# mixer-MAC-24.net
KiCad netlist of a schematic drawn in EAGLE
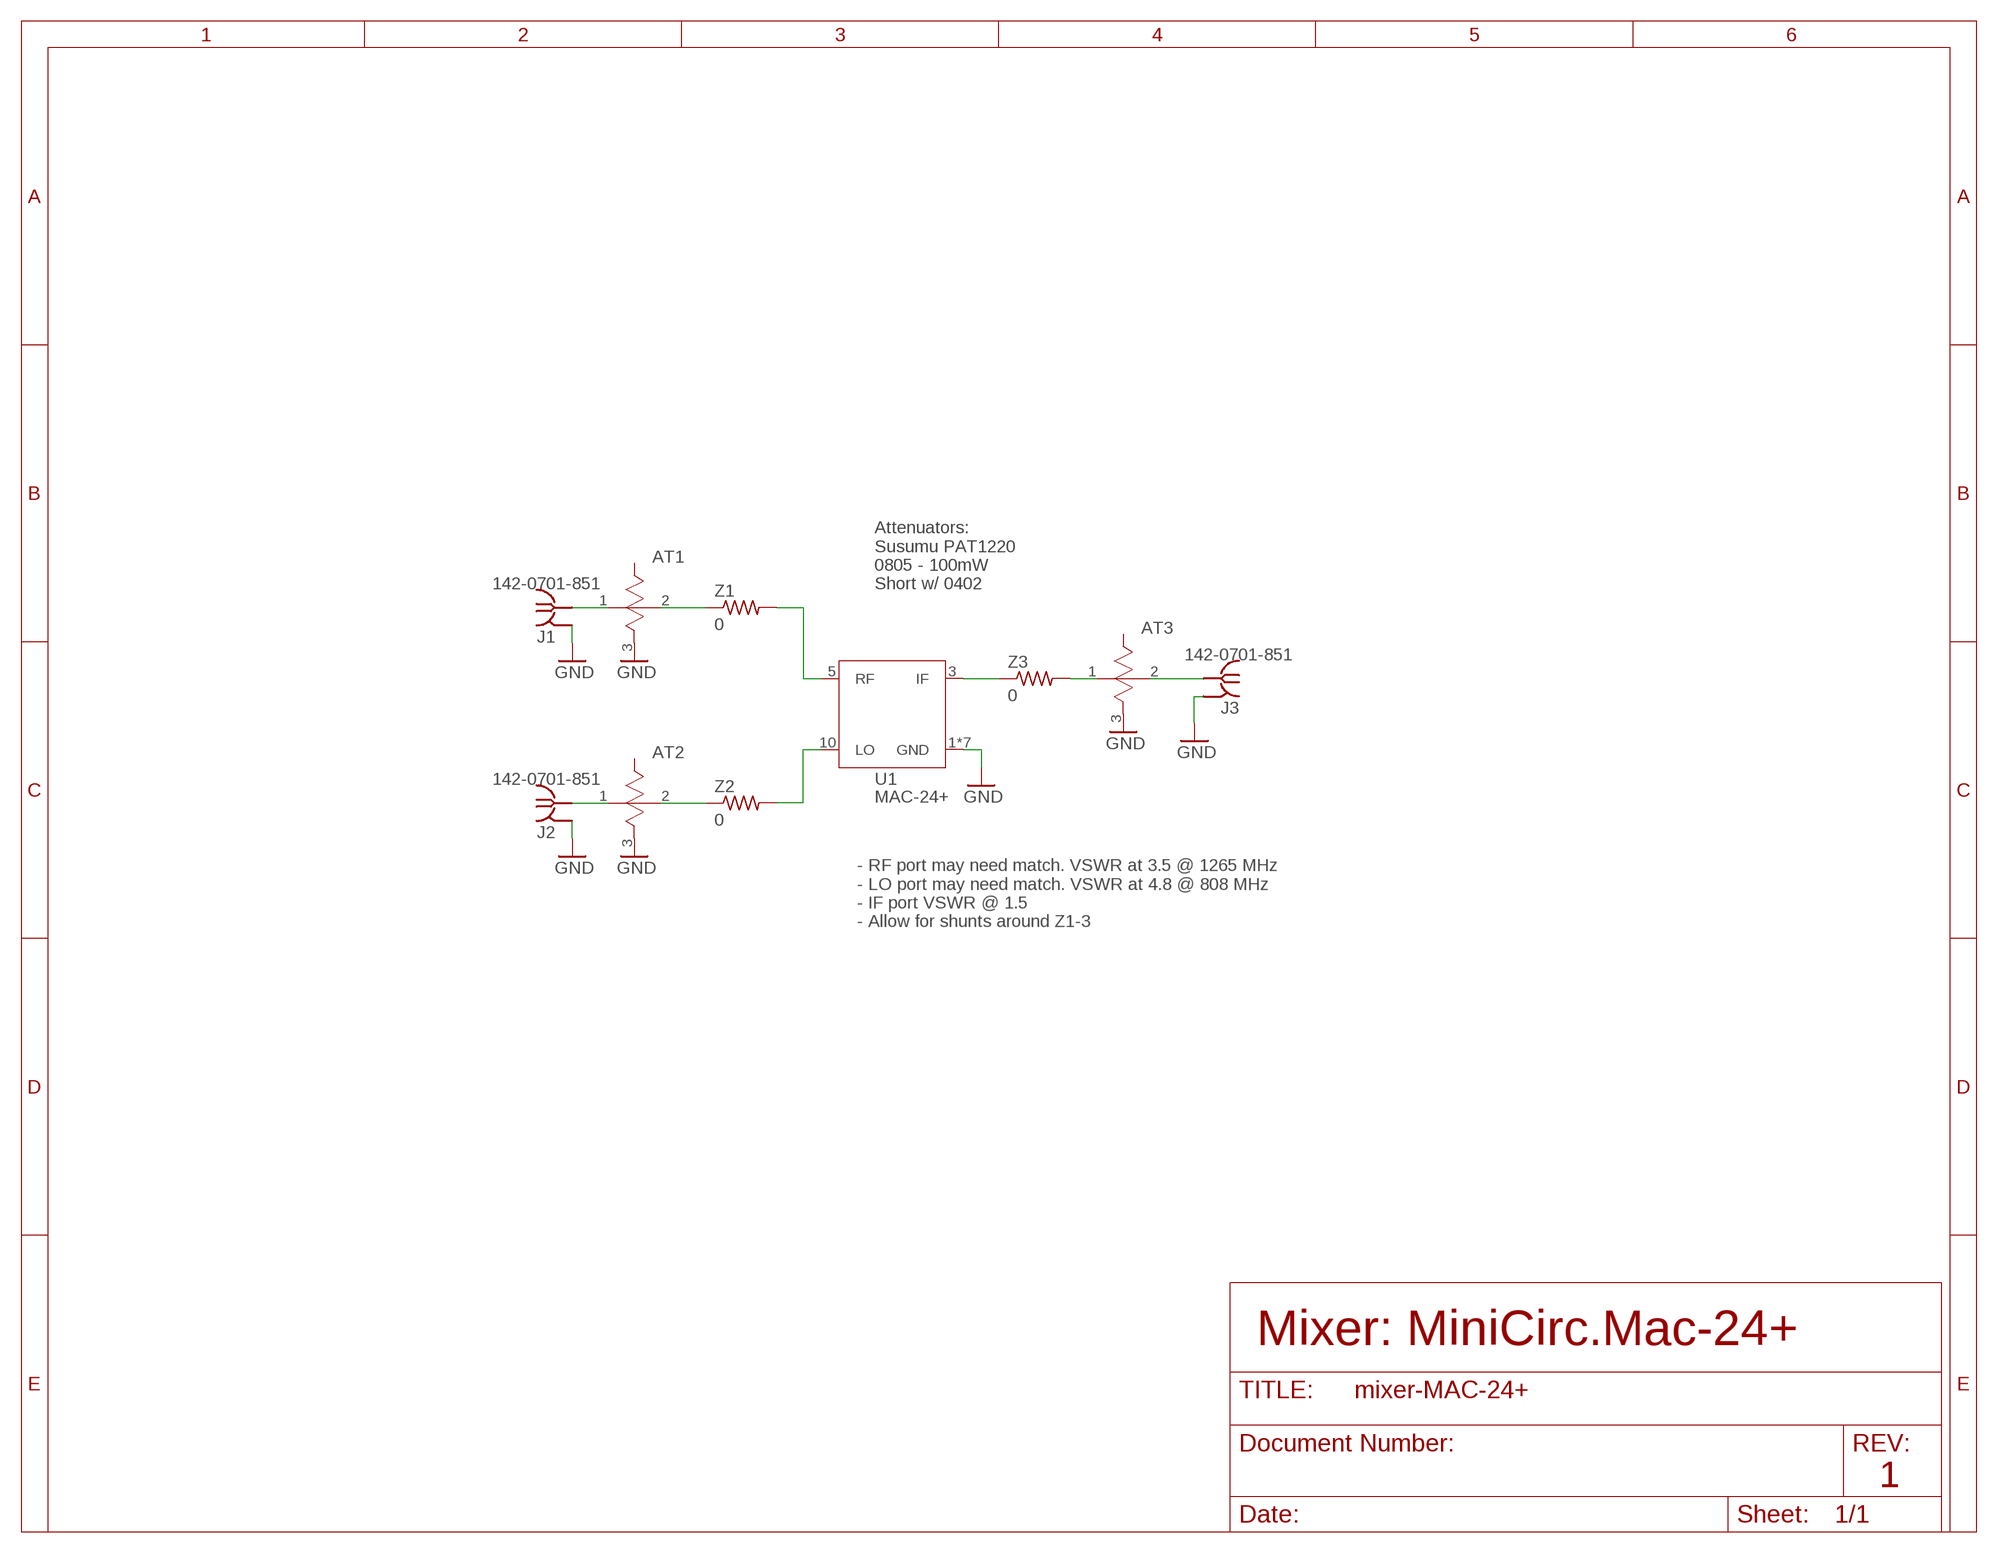
[diagram p0: schematic, sheet 1]

(export (version "E")
  (design (tool "Eeschema 10.0.6"))
  (components
    (comp (ref "AT1")
      (value "PAT1220")
      (footprint "eagle-import:0805")
      (libsource (lib "eagle-import") (part "PAT1220"))
    )
    (comp (ref "AT2")
      (value "PAT1220")
      (footprint "eagle-import:0805")
      (libsource (lib "eagle-import") (part "PAT1220"))
    )
    (comp (ref "AT3")
      (value "PAT1220")
      (footprint "eagle-import:0805")
      (libsource (lib "eagle-import") (part "PAT1220"))
    )
    (comp (ref "J1")
      (value "142-0701-851")
      (footprint "eagle-import:142-0701-851")
      (libsource (lib "eagle-import") (part "142-0701-851"))
    )
    (comp (ref "J2")
      (value "142-0701-851")
      (footprint "eagle-import:142-0701-851")
      (libsource (lib "eagle-import") (part "142-0701-851"))
    )
    (comp (ref "J3")
      (value "142-0701-851")
      (footprint "eagle-import:142-0701-851")
      (libsource (lib "eagle-import") (part "142-0701-851"))
    )
    (comp (ref "U1")
      (value "MAC-24+")
      (footprint "eagle-import:MAC-24+")
      (libsource (lib "eagle-import") (part "MAC-24+"))
    )
    (comp (ref "Z1")
      (value "0")
      (footprint "eagle-import:.0402-C-NOSILK")
      (libsource (lib "eagle-import") (part "R-US_0402-C-NOSILK"))
    )
    (comp (ref "Z2")
      (value "0")
      (footprint "eagle-import:.0402-C-NOSILK")
      (libsource (lib "eagle-import") (part "R-US_0402-C-NOSILK"))
    )
    (comp (ref "Z3")
      (value "0")
      (footprint "eagle-import:.0402-C-NOSILK")
      (libsource (lib "eagle-import") (part "R-US_0402-C-NOSILK"))
    )
  )
  (nets
    (net (code "1") (name "GND") (class "Default")
      (node (ref "AT1") (pin "3") (pinfunction "GND_3") (pintype "power_in"))
      (node (ref "AT2") (pin "3") (pinfunction "GND_3") (pintype "power_in"))
      (node (ref "AT3") (pin "3") (pinfunction "GND_3") (pintype "power_in"))
      (node (ref "J1") (pin "GND1") (pinfunction "GND_GND1") (pintype "bidirectional"))
      (node (ref "J1") (pin "GND2") (pinfunction "GND_GND2") (pintype "bidirectional"))
      (node (ref "J1") (pin "GND3") (pinfunction "GND_GND3") (pintype "bidirectional"))
      (node (ref "J1") (pin "GND4") (pinfunction "GND_GND4") (pintype "bidirectional"))
      (node (ref "J2") (pin "GND1") (pinfunction "GND_GND1") (pintype "bidirectional"))
      (node (ref "J2") (pin "GND2") (pinfunction "GND_GND2") (pintype "bidirectional"))
      (node (ref "J2") (pin "GND3") (pinfunction "GND_GND3") (pintype "bidirectional"))
      (node (ref "J2") (pin "GND4") (pinfunction "GND_GND4") (pintype "bidirectional"))
      (node (ref "J3") (pin "GND1") (pinfunction "GND_GND1") (pintype "bidirectional"))
      (node (ref "J3") (pin "GND2") (pinfunction "GND_GND2") (pintype "bidirectional"))
      (node (ref "J3") (pin "GND3") (pinfunction "GND_GND3") (pintype "bidirectional"))
      (node (ref "J3") (pin "GND4") (pinfunction "GND_GND4") (pintype "bidirectional"))
      (node (ref "U1") (pin "1") (pinfunction "GND_1") (pintype "power_in"))
      (node (ref "U1") (pin "2") (pinfunction "GND_2") (pintype "power_in"))
      (node (ref "U1") (pin "4") (pinfunction "GND_4") (pintype "power_in"))
      (node (ref "U1") (pin "6") (pinfunction "GND_6") (pintype "power_in"))
      (node (ref "U1") (pin "7") (pinfunction "GND_7") (pintype "power_in"))
      (node (ref "U1") (pin "8") (pinfunction "GND_8") (pintype "power_in"))
      (node (ref "U1") (pin "9") (pinfunction "GND_9") (pintype "power_in"))
    )
    (net (code "2") (name "Net-(AT1-Pad2)") (class "Default")
      (node (ref "AT1") (pin "2") (pinfunction "2_2") (pintype "bidirectional"))
      (node (ref "Z1") (pin "1") (pinfunction "1_1") (pintype "passive"))
    )
    (net (code "3") (name "Net-(AT2-Pad2)") (class "Default")
      (node (ref "AT2") (pin "2") (pinfunction "2_2") (pintype "bidirectional"))
      (node (ref "Z2") (pin "1") (pinfunction "1_1") (pintype "passive"))
    )
    (net (code "4") (name "Net-(AT3-Pad1)") (class "Default")
      (node (ref "AT3") (pin "1") (pinfunction "1_1") (pintype "bidirectional"))
      (node (ref "Z3") (pin "2") (pinfunction "2_2") (pintype "passive"))
    )
    (net (code "5") (name "Net-(J1-RF)") (class "Default")
      (node (ref "AT1") (pin "1") (pinfunction "1_1") (pintype "bidirectional"))
      (node (ref "J1") (pin "RF1") (pinfunction "RF_RF1") (pintype "bidirectional"))
    )
    (net (code "6") (name "Net-(J2-RF)") (class "Default")
      (node (ref "AT2") (pin "1") (pinfunction "1_1") (pintype "bidirectional"))
      (node (ref "J2") (pin "RF1") (pinfunction "RF_RF1") (pintype "bidirectional"))
    )
    (net (code "7") (name "Net-(J3-RF)") (class "Default")
      (node (ref "AT3") (pin "2") (pinfunction "2_2") (pintype "bidirectional"))
      (node (ref "J3") (pin "RF1") (pinfunction "RF_RF1") (pintype "bidirectional"))
    )
    (net (code "8") (name "Net-(U1-IF)") (class "Default")
      (node (ref "U1") (pin "3") (pinfunction "IF_3") (pintype "output"))
      (node (ref "Z3") (pin "1") (pinfunction "1_1") (pintype "passive"))
    )
    (net (code "9") (name "Net-(U1-LO)") (class "Default")
      (node (ref "U1") (pin "10") (pinfunction "LO_10") (pintype "input"))
      (node (ref "Z2") (pin "2") (pinfunction "2_2") (pintype "passive"))
    )
    (net (code "10") (name "Net-(U1-RF)") (class "Default")
      (node (ref "U1") (pin "5") (pinfunction "RF_5") (pintype "input"))
      (node (ref "Z1") (pin "2") (pinfunction "2_2") (pintype "passive"))
    )
  )
)
